# 6_uart_esc_i2c.net
KiCad netlist of a schematic drawn in Altium Designer
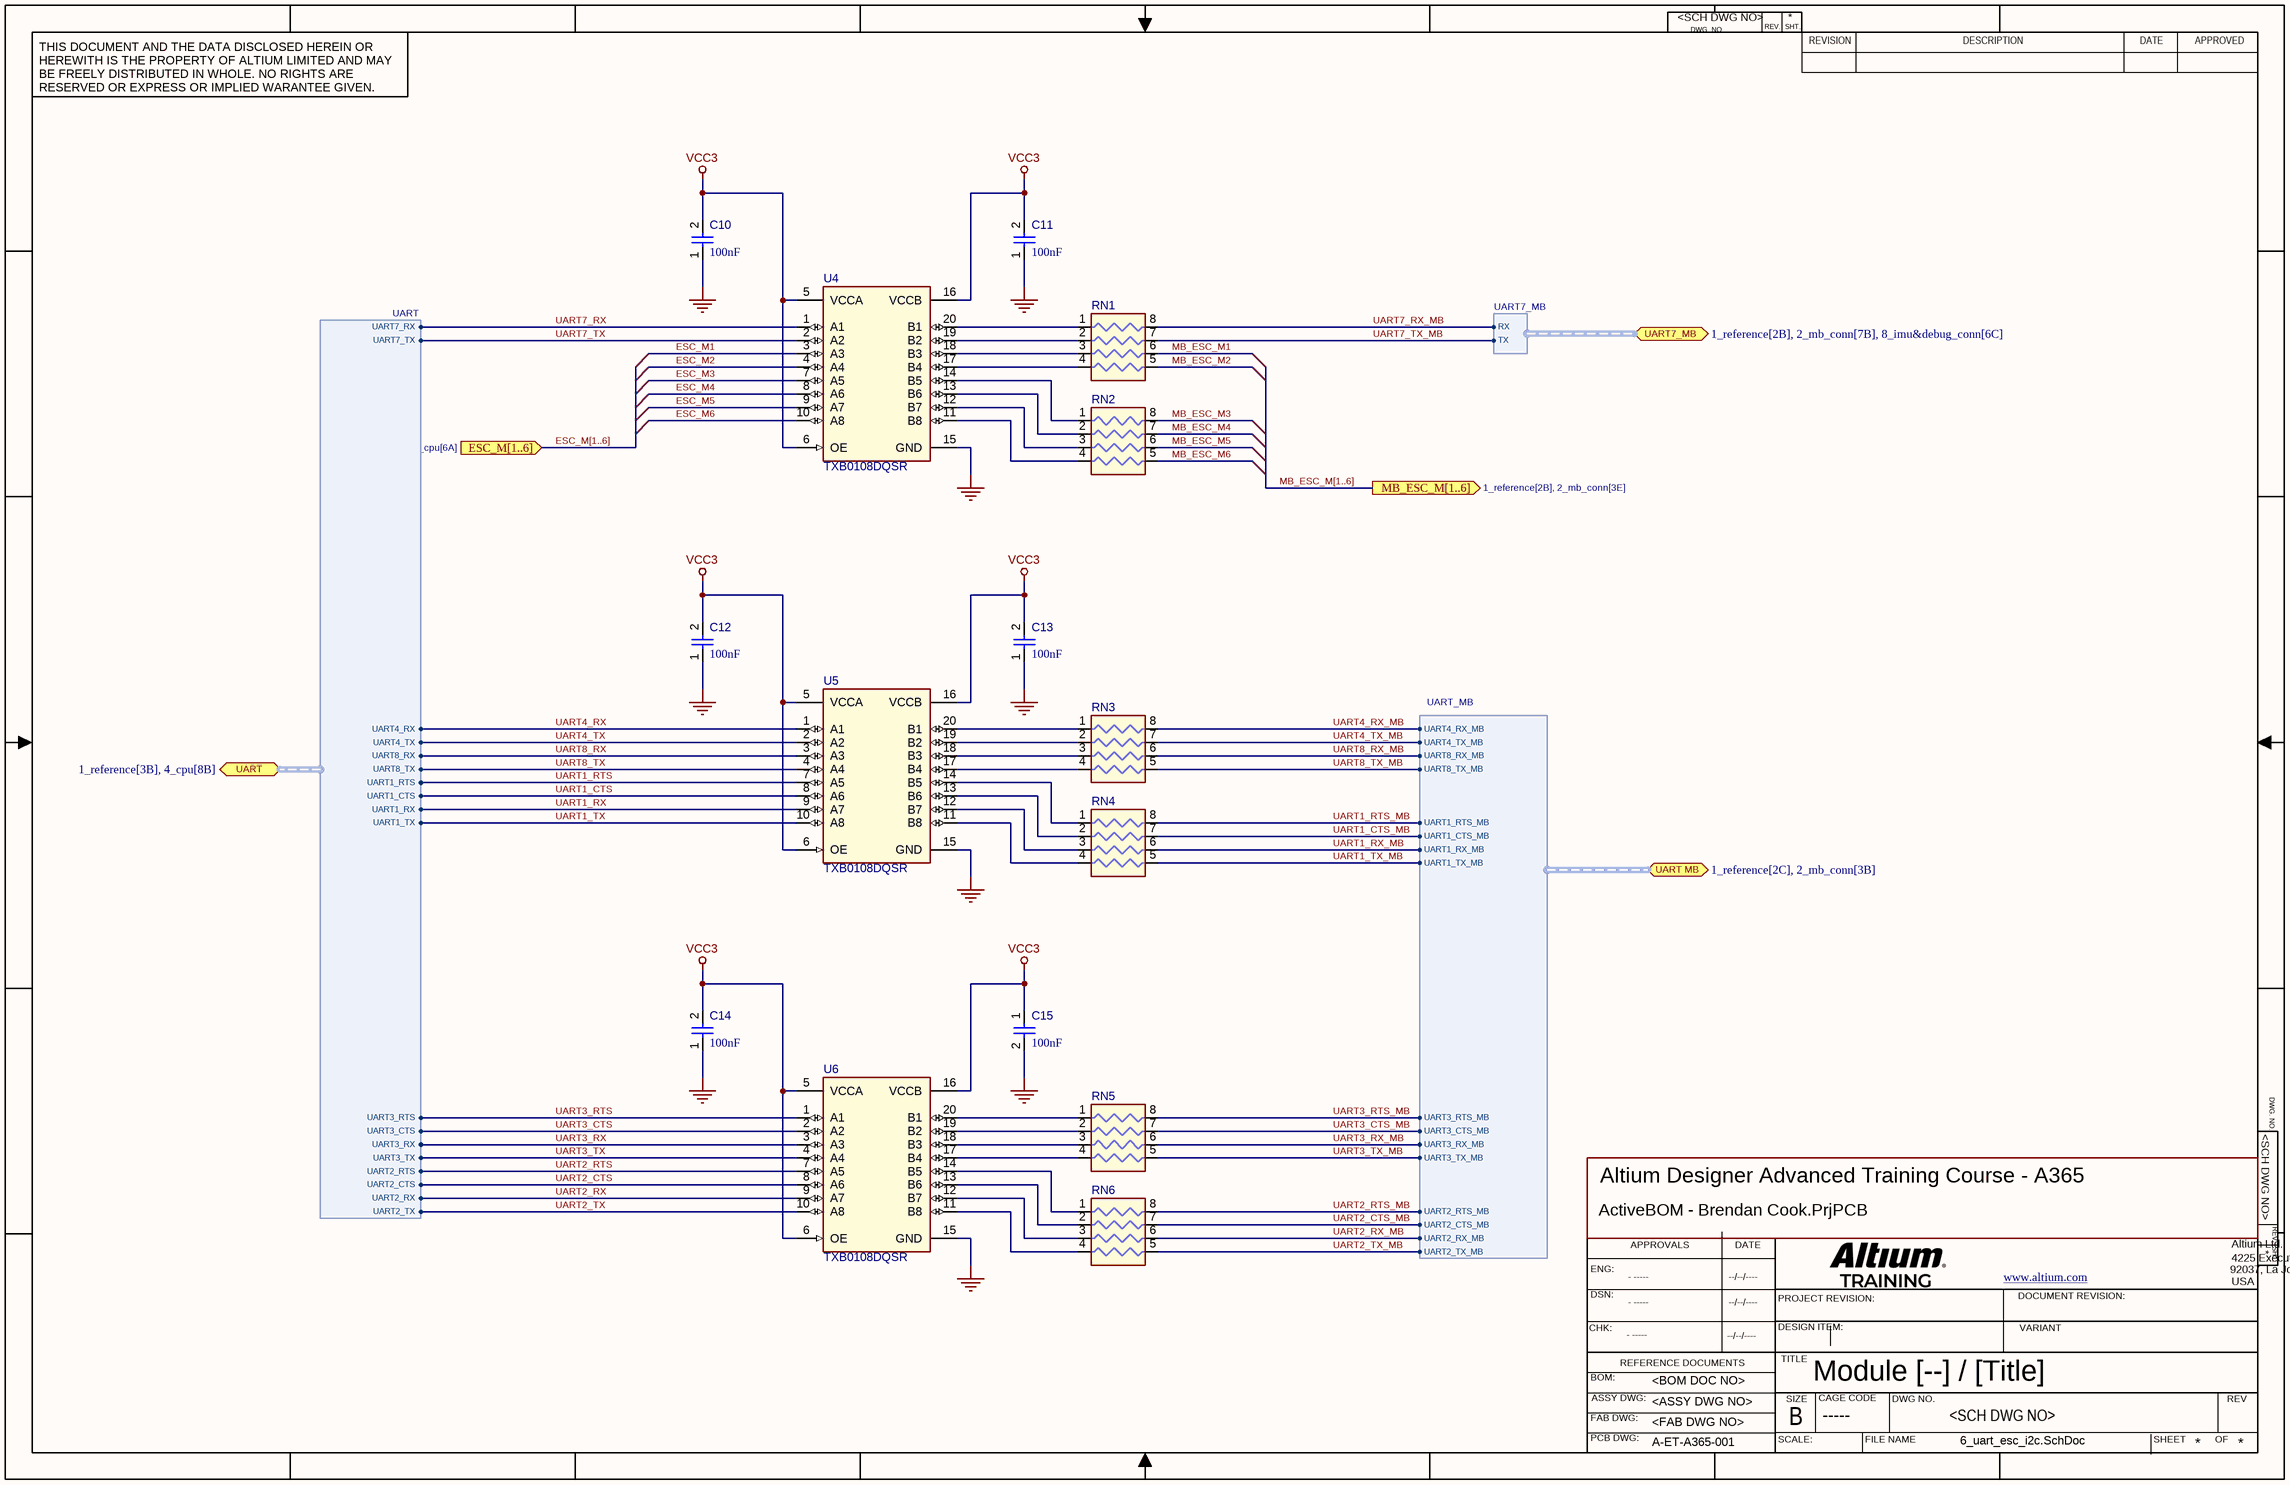
[diagram p0: 6_uart_esc_i2c.SchDoc]

(export (version "E")
  (design (tool "Eeschema 10.0.6"))
  (components
    (comp (ref "C10")
      (value "100nF")
      (footprint "CAPC0402(1005)60_L")
      (description "Chip Capacitor, 100nF +/-20%, 10V, 0402, Thickness 0.6 mm")
      (fields (field (name "TOLERANCE") "20%") (field (name "Comment") "Capacitor 100nF +/-20% 10V 0402"))
      (libsource (lib "MHH -  Altium Advanced Course A365 01") (part "CAP-NP-2"))
    )
    (comp (ref "C11")
      (value "100nF")
      (footprint "CAPC0402(1005)60_L")
      (description "Chip Capacitor, 100nF +/-20%, 10V, 0402, Thickness 0.6 mm")
      (fields (field (name "TOLERANCE") "20%") (field (name "Comment") "Capacitor 100nF +/-20% 10V 0402"))
      (libsource (lib "MHH -  Altium Advanced Course A365 01") (part "CAP-NP-2"))
    )
    (comp (ref "C12")
      (value "100nF")
      (footprint "CAPC0402(1005)60_L")
      (description "Chip Capacitor, 100nF +/-20%, 10V, 0402, Thickness 0.6 mm")
      (fields (field (name "TOLERANCE") "20%") (field (name "Comment") "Capacitor 100nF +/-20% 10V 0402"))
      (libsource (lib "MHH -  Altium Advanced Course A365 01") (part "CAP-NP-2"))
    )
    (comp (ref "C13")
      (value "100nF")
      (footprint "CAPC0402(1005)60_L")
      (description "Chip Capacitor, 100nF +/-20%, 10V, 0402, Thickness 0.6 mm")
      (fields (field (name "TOLERANCE") "20%") (field (name "Comment") "Capacitor 100nF +/-20% 10V 0402"))
      (libsource (lib "MHH -  Altium Advanced Course A365 01") (part "CAP-NP-2"))
    )
    (comp (ref "C14")
      (value "100nF")
      (footprint "CAPC0402(1005)60_L")
      (description "Chip Capacitor, 100nF +/-20%, 10V, 0402, Thickness 0.6 mm")
      (fields (field (name "TOLERANCE") "20%") (field (name "Comment") "Capacitor 100nF +/-20% 10V 0402"))
      (libsource (lib "MHH -  Altium Advanced Course A365 01") (part "CAP-NP-2"))
    )
    (comp (ref "C15")
      (value "100nF")
      (footprint "CAPC0402(1005)60_L")
      (description "Chip Capacitor, 100nF +/-20%, 10V, 0402, Thickness 0.6 mm")
      (fields (field (name "TOLERANCE") "20%") (field (name "Comment") "Capacitor 100nF +/-20% 10V 0402"))
      (libsource (lib "MHH -  Altium Advanced Course A365 01") (part "CAP-NP-2"))
    )
    (comp (ref "RN1")
      (value "Resistor 200R +/-5% 0402 62.5 mW")
      (footprint "Panasonic_EXB28")
      (fields (field (name "TOLERANCE") "5%") (field (name "POWER") "62.5mW"))
      (libsource (lib "MHH -  Altium Advanced Course A365 01") (part "RES-P-4"))
    )
    (comp (ref "RN2")
      (value "Resistor 200R +/-5% 0402 62.5 mW")
      (footprint "Panasonic_EXB28")
      (fields (field (name "TOLERANCE") "5%") (field (name "POWER") "62.5mW"))
      (libsource (lib "MHH -  Altium Advanced Course A365 01") (part "RES-P-4"))
    )
    (comp (ref "RN3")
      (value "Resistor 200R +/-5% 0402 62.5 mW")
      (footprint "Panasonic_EXB28")
      (fields (field (name "TOLERANCE") "5%") (field (name "POWER") "62.5mW"))
      (libsource (lib "MHH -  Altium Advanced Course A365 01") (part "RES-P-4"))
    )
    (comp (ref "RN4")
      (value "Resistor 200R +/-5% 0402 62.5 mW")
      (footprint "Panasonic_EXB28")
      (fields (field (name "TOLERANCE") "5%") (field (name "POWER") "62.5mW"))
      (libsource (lib "MHH -  Altium Advanced Course A365 01") (part "RES-P-4"))
    )
    (comp (ref "RN5")
      (value "Resistor 200R +/-5% 0402 62.5 mW")
      (footprint "Panasonic_EXB28")
      (fields (field (name "TOLERANCE") "5%") (field (name "POWER") "62.5mW"))
      (libsource (lib "MHH -  Altium Advanced Course A365 01") (part "RES-P-4"))
    )
    (comp (ref "RN6")
      (value "Resistor 200R +/-5% 0402 62.5 mW")
      (footprint "Panasonic_EXB28")
      (fields (field (name "TOLERANCE") "5%") (field (name "POWER") "62.5mW"))
      (libsource (lib "MHH -  Altium Advanced Course A365 01") (part "RES-P-4"))
    )
    (comp (ref "U4")
      (value "TXB0108DQSR")
      (footprint "DQS0020A_V")
      (libsource (lib "MHH -  Altium Advanced Course A365 01") (part "CMP-00162-7"))
    )
    (comp (ref "U5")
      (value "TXB0108DQSR")
      (footprint "DQS0020A_V")
      (libsource (lib "MHH -  Altium Advanced Course A365 01") (part "CMP-00162-7"))
    )
    (comp (ref "U6")
      (value "TXB0108DQSR")
      (footprint "DQS0020A_V")
      (libsource (lib "MHH -  Altium Advanced Course A365 01") (part "CMP-00162-7"))
    )
  )
  (nets
    (net (code "4") (name "/ESC_M1") (class "Default")
      (node (ref "U4") (pin "3") (pinfunction "A3_3") (pintype "bidirectional"))
    )
    (net (code "5") (name "/ESC_M2") (class "Default")
      (node (ref "U4") (pin "4") (pinfunction "A4_4") (pintype "bidirectional"))
    )
    (net (code "6") (name "/ESC_M3") (class "Default")
      (node (ref "U4") (pin "7") (pinfunction "A5_7") (pintype "bidirectional"))
    )
    (net (code "7") (name "/ESC_M4") (class "Default")
      (node (ref "U4") (pin "8") (pinfunction "A6_8") (pintype "bidirectional"))
    )
    (net (code "8") (name "/ESC_M5") (class "Default")
      (node (ref "U4") (pin "9") (pinfunction "A7_9") (pintype "bidirectional"))
    )
    (net (code "9") (name "/ESC_M6") (class "Default")
      (node (ref "U4") (pin "10") (pinfunction "A8_10") (pintype "bidirectional"))
    )
    (net (code "11") (name "/MB_ESC_M1") (class "Default")
      (node (ref "RN1") (pin "6") (pinfunction "2_6") (pintype "passive"))
    )
    (net (code "12") (name "/MB_ESC_M2") (class "Default")
      (node (ref "RN1") (pin "5") (pinfunction "2_5") (pintype "passive"))
    )
    (net (code "13") (name "/MB_ESC_M3") (class "Default")
      (node (ref "RN2") (pin "8") (pinfunction "2_8") (pintype "passive"))
    )
    (net (code "14") (name "/MB_ESC_M4") (class "Default")
      (node (ref "RN2") (pin "7") (pinfunction "2_7") (pintype "passive"))
    )
    (net (code "15") (name "/MB_ESC_M5") (class "Default")
      (node (ref "RN2") (pin "6") (pinfunction "2_6") (pintype "passive"))
    )
    (net (code "16") (name "/MB_ESC_M6") (class "Default")
      (node (ref "RN2") (pin "5") (pinfunction "2_5") (pintype "passive"))
    )
    (net (code "18") (name "/UART1_CTS") (class "Default")
      (node (ref "U5") (pin "8") (pinfunction "A6_8") (pintype "bidirectional"))
    )
    (net (code "19") (name "/UART1_CTS_MB") (class "Default")
      (node (ref "RN4") (pin "7") (pinfunction "2_7") (pintype "passive"))
    )
    (net (code "20") (name "/UART1_RTS") (class "Default")
      (node (ref "U5") (pin "7") (pinfunction "A5_7") (pintype "bidirectional"))
    )
    (net (code "21") (name "/UART1_RTS_MB") (class "Default")
      (node (ref "RN4") (pin "8") (pinfunction "2_8") (pintype "passive"))
    )
    (net (code "22") (name "/UART1_RX") (class "Default")
      (node (ref "U5") (pin "9") (pinfunction "A7_9") (pintype "bidirectional"))
    )
    (net (code "23") (name "/UART1_RX_MB") (class "Default")
      (node (ref "RN4") (pin "6") (pinfunction "2_6") (pintype "passive"))
    )
    (net (code "24") (name "/UART1_TX") (class "Default")
      (node (ref "U5") (pin "10") (pinfunction "A8_10") (pintype "bidirectional"))
    )
    (net (code "25") (name "/UART1_TX_MB") (class "Default")
      (node (ref "RN4") (pin "5") (pinfunction "2_5") (pintype "passive"))
    )
    (net (code "26") (name "/UART2_CTS") (class "Default")
      (node (ref "U6") (pin "8") (pinfunction "A6_8") (pintype "bidirectional"))
    )
    (net (code "27") (name "/UART2_CTS_MB") (class "Default")
      (node (ref "RN6") (pin "7") (pinfunction "2_7") (pintype "passive"))
    )
    (net (code "28") (name "/UART2_RTS") (class "Default")
      (node (ref "U6") (pin "7") (pinfunction "A5_7") (pintype "bidirectional"))
    )
    (net (code "29") (name "/UART2_RTS_MB") (class "Default")
      (node (ref "RN6") (pin "8") (pinfunction "2_8") (pintype "passive"))
    )
    (net (code "30") (name "/UART2_RX") (class "Default")
      (node (ref "U6") (pin "9") (pinfunction "A7_9") (pintype "bidirectional"))
    )
    (net (code "31") (name "/UART2_RX_MB") (class "Default")
      (node (ref "RN6") (pin "6") (pinfunction "2_6") (pintype "passive"))
    )
    (net (code "32") (name "/UART2_TX") (class "Default")
      (node (ref "U6") (pin "10") (pinfunction "A8_10") (pintype "bidirectional"))
    )
    (net (code "33") (name "/UART2_TX_MB") (class "Default")
      (node (ref "RN6") (pin "5") (pinfunction "2_5") (pintype "passive"))
    )
    (net (code "34") (name "/UART3_CTS") (class "Default")
      (node (ref "U6") (pin "2") (pinfunction "A2_2") (pintype "bidirectional"))
    )
    (net (code "35") (name "/UART3_CTS_MB") (class "Default")
      (node (ref "RN5") (pin "7") (pinfunction "2_7") (pintype "passive"))
    )
    (net (code "36") (name "/UART3_RTS") (class "Default")
      (node (ref "U6") (pin "1") (pinfunction "A1_1") (pintype "bidirectional"))
    )
    (net (code "37") (name "/UART3_RTS_MB") (class "Default")
      (node (ref "RN5") (pin "8") (pinfunction "2_8") (pintype "passive"))
    )
    (net (code "38") (name "/UART3_RX") (class "Default")
      (node (ref "U6") (pin "3") (pinfunction "A3_3") (pintype "bidirectional"))
    )
    (net (code "39") (name "/UART3_RX_MB") (class "Default")
      (node (ref "RN5") (pin "6") (pinfunction "2_6") (pintype "passive"))
    )
    (net (code "40") (name "/UART3_TX") (class "Default")
      (node (ref "U6") (pin "4") (pinfunction "A4_4") (pintype "bidirectional"))
    )
    (net (code "41") (name "/UART3_TX_MB") (class "Default")
      (node (ref "RN5") (pin "5") (pinfunction "2_5") (pintype "passive"))
    )
    (net (code "42") (name "/UART4_RX") (class "Default")
      (node (ref "U5") (pin "1") (pinfunction "A1_1") (pintype "bidirectional"))
    )
    (net (code "43") (name "/UART4_RX_MB") (class "Default")
      (node (ref "RN3") (pin "8") (pinfunction "2_8") (pintype "passive"))
    )
    (net (code "44") (name "/UART4_TX") (class "Default")
      (node (ref "U5") (pin "2") (pinfunction "A2_2") (pintype "bidirectional"))
    )
    (net (code "45") (name "/UART4_TX_MB") (class "Default")
      (node (ref "RN3") (pin "7") (pinfunction "2_7") (pintype "passive"))
    )
    (net (code "46") (name "/UART7_RX") (class "Default")
      (node (ref "U4") (pin "1") (pinfunction "A1_1") (pintype "bidirectional"))
    )
    (net (code "47") (name "/UART7_RX_MB") (class "Default")
      (node (ref "RN1") (pin "8") (pinfunction "2_8") (pintype "passive"))
    )
    (net (code "48") (name "/UART7_TX") (class "Default")
      (node (ref "U4") (pin "2") (pinfunction "A2_2") (pintype "bidirectional"))
    )
    (net (code "49") (name "/UART7_TX_MB") (class "Default")
      (node (ref "RN1") (pin "7") (pinfunction "2_7") (pintype "passive"))
    )
    (net (code "50") (name "/UART8_RX") (class "Default")
      (node (ref "U5") (pin "3") (pinfunction "A3_3") (pintype "bidirectional"))
    )
    (net (code "51") (name "/UART8_RX_MB") (class "Default")
      (node (ref "RN3") (pin "6") (pinfunction "2_6") (pintype "passive"))
    )
    (net (code "52") (name "/UART8_TX") (class "Default")
      (node (ref "U5") (pin "4") (pinfunction "A4_4") (pintype "bidirectional"))
    )
    (net (code "53") (name "/UART8_TX_MB") (class "Default")
      (node (ref "RN3") (pin "5") (pinfunction "2_5") (pintype "passive"))
    )
    (net (code "57") (name "GND") (class "Default")
      (node (ref "C10") (pin "1") (pinfunction "1_1") (pintype "passive"))
      (node (ref "C11") (pin "1") (pinfunction "1_1") (pintype "passive"))
      (node (ref "C12") (pin "1") (pinfunction "1_1") (pintype "passive"))
      (node (ref "C13") (pin "1") (pinfunction "1_1") (pintype "passive"))
      (node (ref "C14") (pin "1") (pinfunction "1_1") (pintype "passive"))
      (node (ref "C15") (pin "2") (pinfunction "2_2") (pintype "passive"))
      (node (ref "U4") (pin "15") (pinfunction "GND_15") (pintype "power_in"))
      (node (ref "U5") (pin "15") (pinfunction "GND_15") (pintype "power_in"))
      (node (ref "U6") (pin "15") (pinfunction "GND_15") (pintype "power_in"))
    )
    (net (code "58") (name "Net-(U4-B1)") (class "Default")
      (node (ref "RN1") (pin "1") (pinfunction "1_1") (pintype "passive"))
      (node (ref "U4") (pin "20") (pinfunction "B1_20") (pintype "bidirectional"))
    )
    (net (code "59") (name "Net-(U4-B2)") (class "Default")
      (node (ref "RN1") (pin "2") (pinfunction "1_2") (pintype "passive"))
      (node (ref "U4") (pin "19") (pinfunction "B2_19") (pintype "bidirectional"))
    )
    (net (code "60") (name "Net-(U4-B3)") (class "Default")
      (node (ref "RN1") (pin "3") (pinfunction "1_3") (pintype "passive"))
      (node (ref "U4") (pin "18") (pinfunction "B3_18") (pintype "bidirectional"))
    )
    (net (code "61") (name "Net-(U4-B4)") (class "Default")
      (node (ref "RN1") (pin "4") (pinfunction "1_4") (pintype "passive"))
      (node (ref "U4") (pin "17") (pinfunction "B4_17") (pintype "bidirectional"))
    )
    (net (code "62") (name "Net-(U4-B5)") (class "Default")
      (node (ref "RN2") (pin "1") (pinfunction "1_1") (pintype "passive"))
      (node (ref "U4") (pin "14") (pinfunction "B5_14") (pintype "bidirectional"))
    )
    (net (code "63") (name "Net-(U4-B6)") (class "Default")
      (node (ref "RN2") (pin "2") (pinfunction "1_2") (pintype "passive"))
      (node (ref "U4") (pin "13") (pinfunction "B6_13") (pintype "bidirectional"))
    )
    (net (code "64") (name "Net-(U4-B7)") (class "Default")
      (node (ref "RN2") (pin "3") (pinfunction "1_3") (pintype "passive"))
      (node (ref "U4") (pin "12") (pinfunction "B7_12") (pintype "bidirectional"))
    )
    (net (code "65") (name "Net-(U4-B8)") (class "Default")
      (node (ref "RN2") (pin "4") (pinfunction "1_4") (pintype "passive"))
      (node (ref "U4") (pin "11") (pinfunction "B8_11") (pintype "bidirectional"))
    )
    (net (code "66") (name "Net-(U5-B1)") (class "Default")
      (node (ref "RN3") (pin "1") (pinfunction "1_1") (pintype "passive"))
      (node (ref "U5") (pin "20") (pinfunction "B1_20") (pintype "bidirectional"))
    )
    (net (code "67") (name "Net-(U5-B2)") (class "Default")
      (node (ref "RN3") (pin "2") (pinfunction "1_2") (pintype "passive"))
      (node (ref "U5") (pin "19") (pinfunction "B2_19") (pintype "bidirectional"))
    )
    (net (code "68") (name "Net-(U5-B3)") (class "Default")
      (node (ref "RN3") (pin "3") (pinfunction "1_3") (pintype "passive"))
      (node (ref "U5") (pin "18") (pinfunction "B3_18") (pintype "bidirectional"))
    )
    (net (code "69") (name "Net-(U5-B4)") (class "Default")
      (node (ref "RN3") (pin "4") (pinfunction "1_4") (pintype "passive"))
      (node (ref "U5") (pin "17") (pinfunction "B4_17") (pintype "bidirectional"))
    )
    (net (code "70") (name "Net-(U5-B5)") (class "Default")
      (node (ref "RN4") (pin "1") (pinfunction "1_1") (pintype "passive"))
      (node (ref "U5") (pin "14") (pinfunction "B5_14") (pintype "bidirectional"))
    )
    (net (code "71") (name "Net-(U5-B6)") (class "Default")
      (node (ref "RN4") (pin "2") (pinfunction "1_2") (pintype "passive"))
      (node (ref "U5") (pin "13") (pinfunction "B6_13") (pintype "bidirectional"))
    )
    (net (code "72") (name "Net-(U5-B7)") (class "Default")
      (node (ref "RN4") (pin "3") (pinfunction "1_3") (pintype "passive"))
      (node (ref "U5") (pin "12") (pinfunction "B7_12") (pintype "bidirectional"))
    )
    (net (code "73") (name "Net-(U5-B8)") (class "Default")
      (node (ref "RN4") (pin "4") (pinfunction "1_4") (pintype "passive"))
      (node (ref "U5") (pin "11") (pinfunction "B8_11") (pintype "bidirectional"))
    )
    (net (code "74") (name "Net-(U6-B1)") (class "Default")
      (node (ref "RN5") (pin "1") (pinfunction "1_1") (pintype "passive"))
      (node (ref "U6") (pin "20") (pinfunction "B1_20") (pintype "bidirectional"))
    )
    (net (code "75") (name "Net-(U6-B2)") (class "Default")
      (node (ref "RN5") (pin "2") (pinfunction "1_2") (pintype "passive"))
      (node (ref "U6") (pin "19") (pinfunction "B2_19") (pintype "bidirectional"))
    )
    (net (code "76") (name "Net-(U6-B3)") (class "Default")
      (node (ref "RN5") (pin "3") (pinfunction "1_3") (pintype "passive"))
      (node (ref "U6") (pin "18") (pinfunction "B3_18") (pintype "bidirectional"))
    )
    (net (code "77") (name "Net-(U6-B4)") (class "Default")
      (node (ref "RN5") (pin "4") (pinfunction "1_4") (pintype "passive"))
      (node (ref "U6") (pin "17") (pinfunction "B4_17") (pintype "bidirectional"))
    )
    (net (code "78") (name "Net-(U6-B5)") (class "Default")
      (node (ref "RN6") (pin "1") (pinfunction "1_1") (pintype "passive"))
      (node (ref "U6") (pin "14") (pinfunction "B5_14") (pintype "bidirectional"))
    )
    (net (code "79") (name "Net-(U6-B6)") (class "Default")
      (node (ref "RN6") (pin "2") (pinfunction "1_2") (pintype "passive"))
      (node (ref "U6") (pin "13") (pinfunction "B6_13") (pintype "bidirectional"))
    )
    (net (code "80") (name "Net-(U6-B7)") (class "Default")
      (node (ref "RN6") (pin "3") (pinfunction "1_3") (pintype "passive"))
      (node (ref "U6") (pin "12") (pinfunction "B7_12") (pintype "bidirectional"))
    )
    (net (code "81") (name "Net-(U6-B8)") (class "Default")
      (node (ref "RN6") (pin "4") (pinfunction "1_4") (pintype "passive"))
      (node (ref "U6") (pin "11") (pinfunction "B8_11") (pintype "bidirectional"))
    )
    (net (code "82") (name "VCC3") (class "Default")
      (node (ref "C10") (pin "2") (pinfunction "2_2") (pintype "passive"))
      (node (ref "C11") (pin "2") (pinfunction "2_2") (pintype "passive"))
      (node (ref "C12") (pin "2") (pinfunction "2_2") (pintype "passive"))
      (node (ref "C13") (pin "2") (pinfunction "2_2") (pintype "passive"))
      (node (ref "C14") (pin "2") (pinfunction "2_2") (pintype "passive"))
      (node (ref "C15") (pin "1") (pinfunction "1_1") (pintype "passive"))
      (node (ref "U4") (pin "16") (pinfunction "VCCB_16") (pintype "power_in"))
      (node (ref "U4") (pin "5") (pinfunction "VCCA_5") (pintype "power_in"))
      (node (ref "U4") (pin "6") (pinfunction "OE_6") (pintype "input"))
      (node (ref "U5") (pin "16") (pinfunction "VCCB_16") (pintype "power_in"))
      (node (ref "U5") (pin "5") (pinfunction "VCCA_5") (pintype "power_in"))
      (node (ref "U5") (pin "6") (pinfunction "OE_6") (pintype "input"))
      (node (ref "U6") (pin "16") (pinfunction "VCCB_16") (pintype "power_in"))
      (node (ref "U6") (pin "5") (pinfunction "VCCA_5") (pintype "power_in"))
      (node (ref "U6") (pin "6") (pinfunction "OE_6") (pintype "input"))
    )
  )
)
